# PCIE_X1_36PIN_1.net
KiCad netlist of a schematic drawn in Altium Designer
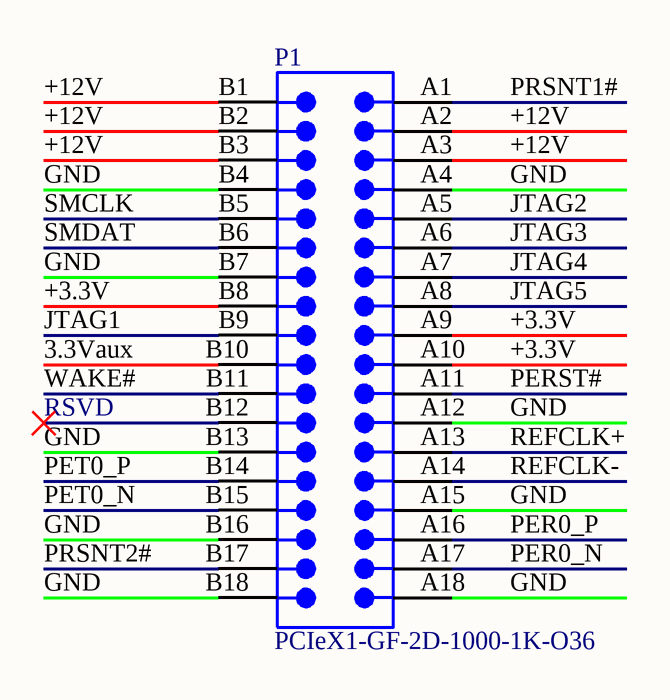
[diagram p0: PCIE_X1_36PIN_1.SchDoc]

(export (version "E")
  (design (tool "Eeschema 10.0.6"))
  (components
    (comp (ref "P1")
      (value "PCIeX1-GF-2D-1000-1K-O36")
      (footprint "PCIeX1-GF-2D-1000-1K-O36")
      (description "Golden finger, PCIeX1, Dual, Opposite, Pitch 1mm, 36-Position")
      (fields (field (name "PUBLISHER") "Altium"))
      (libsource (lib "altium-import") (part "root_3_PCIeX1-GF-2D-1000-1K-O36_"))
    )
  )
  (nets
    (net (code "1") (name "/+3.3V") (class "Default")
      (node (ref "P1") (pin "A10") (pinfunction "A10_A10") (pintype "passive"))
      (node (ref "P1") (pin "A9") (pinfunction "A9_A9") (pintype "passive"))
      (node (ref "P1") (pin "B8") (pinfunction "B8_B8") (pintype "passive"))
    )
    (net (code "2") (name "/+12V") (class "Default")
      (node (ref "P1") (pin "A2") (pinfunction "A2_A2") (pintype "passive"))
      (node (ref "P1") (pin "A3") (pinfunction "A3_A3") (pintype "passive"))
      (node (ref "P1") (pin "B1") (pinfunction "B1_B1") (pintype "passive"))
      (node (ref "P1") (pin "B2") (pinfunction "B2_B2") (pintype "passive"))
      (node (ref "P1") (pin "B3") (pinfunction "B3_B3") (pintype "passive"))
    )
    (net (code "3") (name "/3.3Vaux") (class "Default")
      (node (ref "P1") (pin "B10") (pinfunction "B10_B10") (pintype "passive"))
    )
    (net (code "4") (name "/GND") (class "Default")
      (node (ref "P1") (pin "A12") (pinfunction "A12_A12") (pintype "passive"))
      (node (ref "P1") (pin "A15") (pinfunction "A15_A15") (pintype "passive"))
      (node (ref "P1") (pin "A18") (pinfunction "A18_A18") (pintype "passive"))
      (node (ref "P1") (pin "A4") (pinfunction "A4_A4") (pintype "passive"))
      (node (ref "P1") (pin "B13") (pinfunction "B13_B13") (pintype "passive"))
      (node (ref "P1") (pin "B16") (pinfunction "B16_B16") (pintype "passive"))
      (node (ref "P1") (pin "B18") (pinfunction "B18_B18") (pintype "passive"))
      (node (ref "P1") (pin "B4") (pinfunction "B4_B4") (pintype "passive"))
      (node (ref "P1") (pin "B7") (pinfunction "B7_B7") (pintype "passive"))
    )
    (net (code "5") (name "/JTAG1") (class "Default")
      (node (ref "P1") (pin "B9") (pinfunction "B9_B9") (pintype "passive"))
    )
    (net (code "6") (name "/JTAG2") (class "Default")
      (node (ref "P1") (pin "A5") (pinfunction "A5_A5") (pintype "passive"))
    )
    (net (code "7") (name "/JTAG3") (class "Default")
      (node (ref "P1") (pin "A6") (pinfunction "A6_A6") (pintype "passive"))
    )
    (net (code "8") (name "/JTAG4") (class "Default")
      (node (ref "P1") (pin "A7") (pinfunction "A7_A7") (pintype "passive"))
    )
    (net (code "9") (name "/JTAG5") (class "Default")
      (node (ref "P1") (pin "A8") (pinfunction "A8_A8") (pintype "passive"))
    )
    (net (code "10") (name "/PER0_N") (class "Default")
      (node (ref "P1") (pin "A17") (pinfunction "A17_A17") (pintype "passive"))
    )
    (net (code "11") (name "/PER0_P") (class "Default")
      (node (ref "P1") (pin "A16") (pinfunction "A16_A16") (pintype "passive"))
    )
    (net (code "12") (name "/PERST#") (class "Default")
      (node (ref "P1") (pin "A11") (pinfunction "A11_A11") (pintype "passive"))
    )
    (net (code "13") (name "/PET0_N") (class "Default")
      (node (ref "P1") (pin "B15") (pinfunction "B15_B15") (pintype "passive"))
    )
    (net (code "14") (name "/PET0_P") (class "Default")
      (node (ref "P1") (pin "B14") (pinfunction "B14_B14") (pintype "passive"))
    )
    (net (code "15") (name "/PRSNT1#") (class "Default")
      (node (ref "P1") (pin "A1") (pinfunction "A1_A1") (pintype "passive"))
    )
    (net (code "16") (name "/PRSNT2#") (class "Default")
      (node (ref "P1") (pin "B17") (pinfunction "B17_B17") (pintype "passive"))
    )
    (net (code "17") (name "/REFCLK+") (class "Default")
      (node (ref "P1") (pin "A13") (pinfunction "A13_A13") (pintype "passive"))
    )
    (net (code "18") (name "/REFCLK-") (class "Default")
      (node (ref "P1") (pin "A14") (pinfunction "A14_A14") (pintype "passive"))
    )
    (net (code "19") (name "/SMCLK") (class "Default")
      (node (ref "P1") (pin "B5") (pinfunction "B5_B5") (pintype "passive"))
    )
    (net (code "20") (name "/SMDAT") (class "Default")
      (node (ref "P1") (pin "B6") (pinfunction "B6_B6") (pintype "passive"))
    )
    (net (code "21") (name "/WAKE#") (class "Default")
      (node (ref "P1") (pin "B11") (pinfunction "B11_B11") (pintype "passive"))
    )
    (net (code "22") (name "unconnected-(P1-PadB12)") (class "Default")
      (node (ref "P1") (pin "B12") (pinfunction "B12_B12") (pintype "passive+no_connect"))
    )
  )
)
